# Boost_Stage.net
KiCad netlist of a schematic drawn in Altium Designer
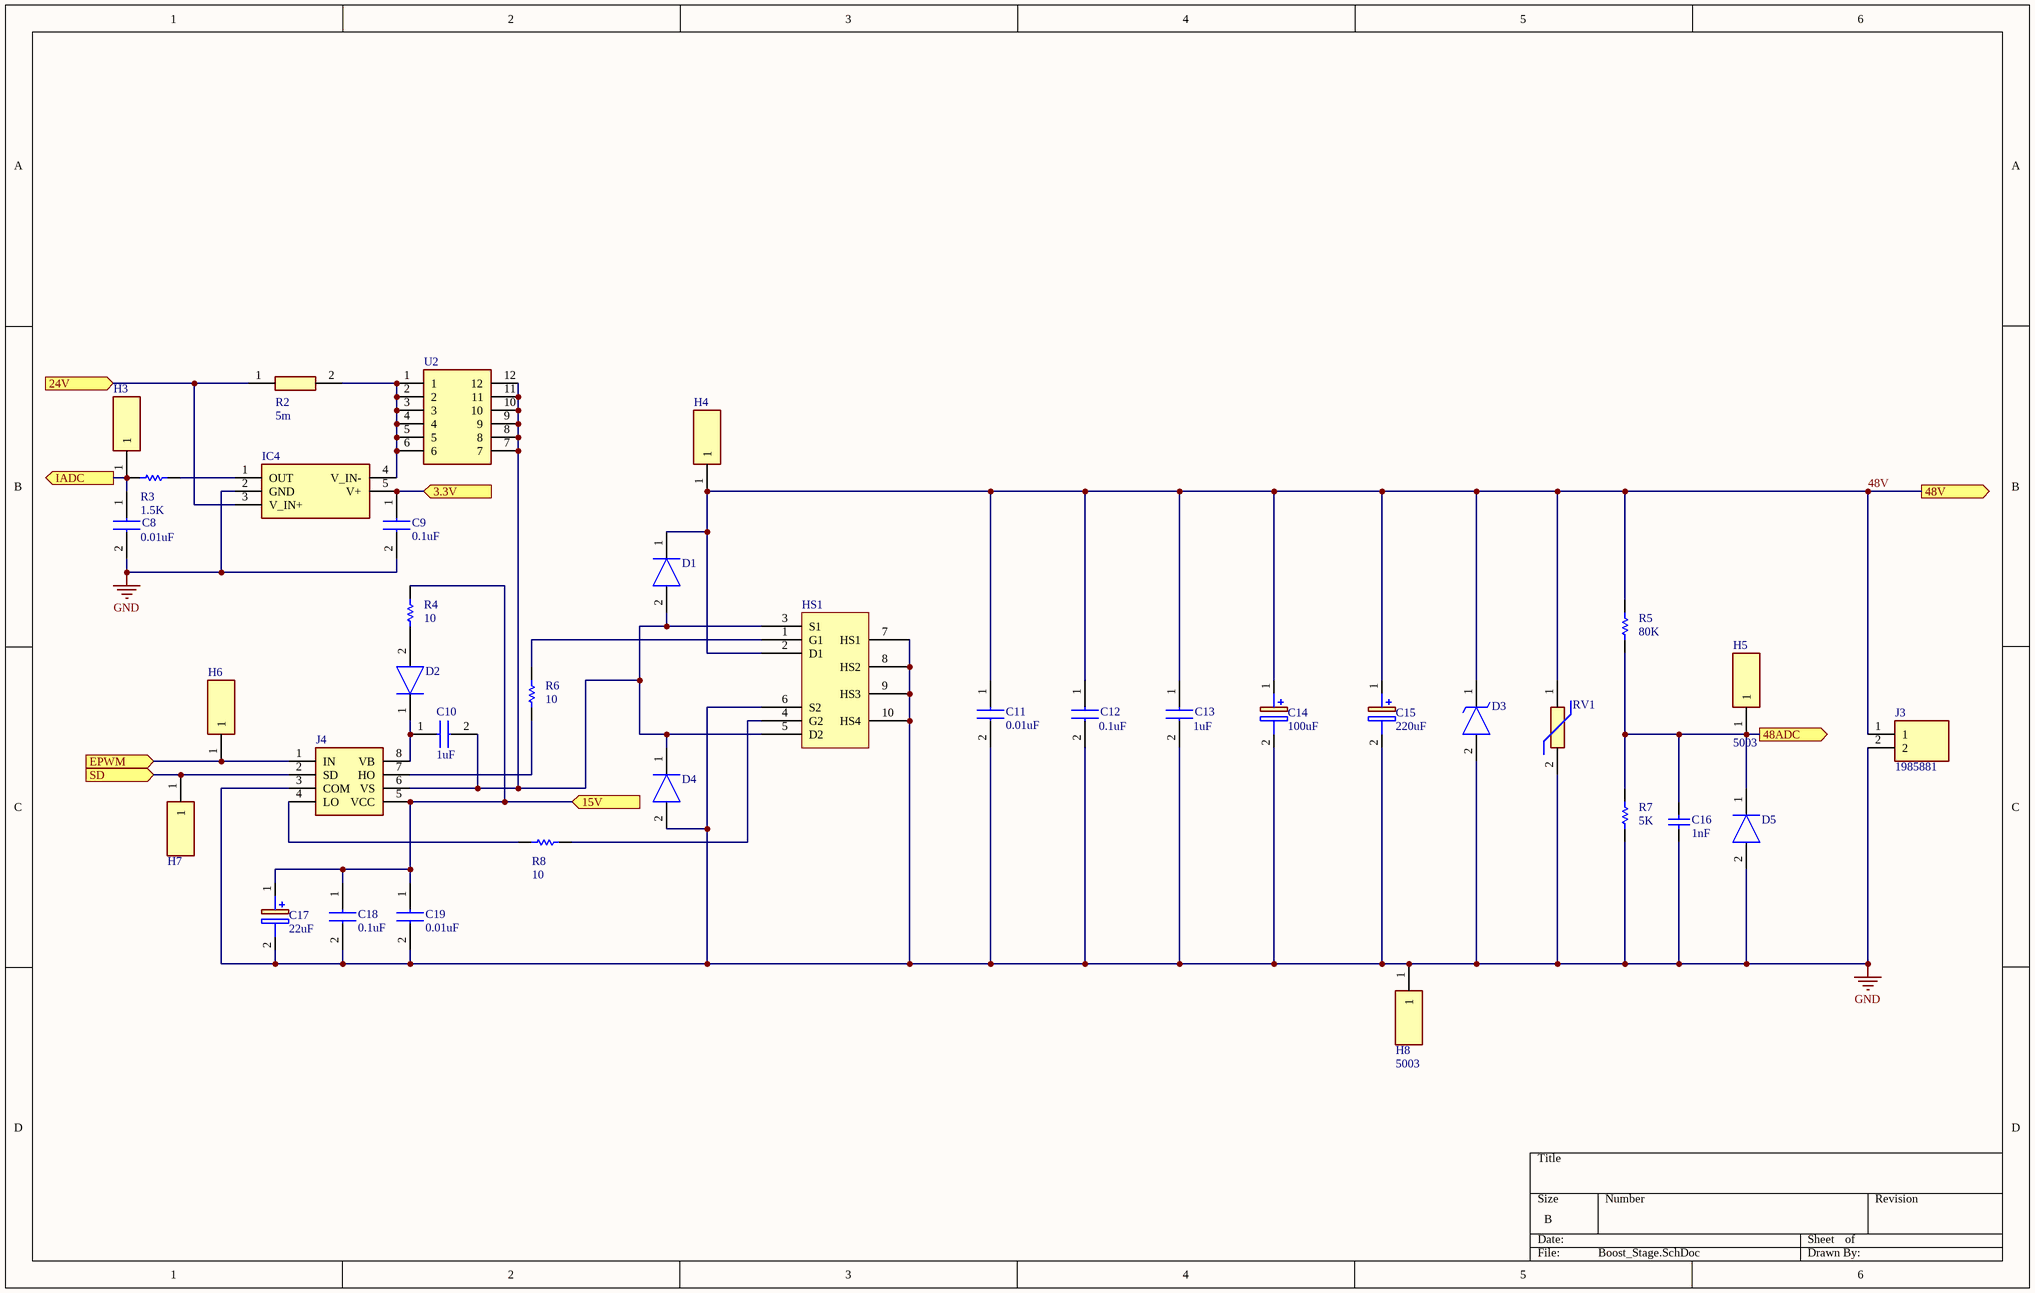
[diagram p0: Boost_Stage.SchDoc]

(export (version "E")
  (design (tool "Eeschema 10.0.6"))
  (components
    (comp (ref "C8")
      (value "0.01uF")
      (footprint "C315C103K5R5TA7990")
      (description "Capacitor 50V")
      (fields (field (name "MANUFACTURER_PART_NUMBER") "C315C103K5R5TA7990"))
      (libsource (lib "ee_453_Schulz") (part "C315C103K5R5TA7990"))
    )
    (comp (ref "C9")
      (value "0.1uF")
      (footprint "K104K10X7RF5UH5")
      (description "Capacitor 50V")
      (fields
        (field (name "MANUFACTURER_PART_NUMBER") "K104K10X7RF5UH5")
        (field (name "MOUSER PART NUMBER") "594-K104K10X7RF5UH5")
      )
      (libsource (lib "ee_453_Schulz") (part "K104K10X7RF5UH5"))
    )
    (comp (ref "C10")
      (value "1uF")
      (footprint "RCE5C1H104J2A2H03B")
      (description "Capacitor")
      (fields
        (field (name "MANUFACTURER_PART_NUMBER") "RDER72A105K2M1H03A")
        (field (name "MOUSER PART NUMBER") "81-RDER72A105K2M1H3A")
      )
      (libsource (lib "ee_453_Schulz") (part "RDER72A105K2M1H03A"))
    )
    (comp (ref "C11")
      (value "0.01uF")
      (footprint "R82(7.2X2.5)")
      (description "Capacitor 100V")
      (fields
        (field (name "MANUFACTURER_PART_NUMBER") "R82EC2100DQ50J")
        (field (name "MOUSER PART NUMBER") "80-R82EC2100DQ50J")
      )
      (libsource (lib "ee_453_Schulz") (part "R82EC2100DQ50J"))
    )
    (comp (ref "C12")
      (value "0.1uF")
      (footprint "ECQE2104JF")
      (description "Capacitor 250V")
      (fields
        (field (name "MANUFACTURER_PART_NUMBER") "ECQ-E2104JF")
        (field (name "MOUSER PART NUMBER") "667-ECQ-E2104JF")
      )
      (libsource (lib "ee_453_Schulz") (part "ECQ-E2104JF"))
    )
    (comp (ref "C13")
      (value "1uF")
      (footprint "ECQE2105KF")
      (description "Capacitor 250V")
      (fields
        (field (name "MANUFACTURER_PART_NUMBER") "ECQ-E2105KF")
        (field (name "MOUSER PART NUMBER") "667-ECQ-E2105KF")
      )
      (libsource (lib "ee_453_Schulz") (part "ECQ-E2105KF"))
    )
    (comp (ref "C14")
      (value "100uF")
      (footprint "CAPPRD500W65D1000H2200")
      (description "Capacitor Polarised 100V")
      (fields
        (field (name "MANUFACTURER_PART_NUMBER") "EEU-FR2A101")
        (field (name "MOUSER PART NUMBER") "667-EEU-FR2A101")
      )
      (libsource (lib "ee_453_Schulz") (part "EEU-FR2A101"))
    )
    (comp (ref "C15")
      (value "220uF")
      (footprint "CAPPRD500W65D1250H2700")
      (description "Capacitor Polarised 100V")
      (fields
        (field (name "MANUFACTURER_PART_NUMBER") "EEU-FS2A221")
        (field (name "MOUSER PART NUMBER") "667-EEU-FS2A221")
      )
      (libsource (lib "ee_453_Schulz") (part "EEU-FS2A221"))
    )
    (comp (ref "C16")
      (value "1nF")
      (footprint "CAPC2013X95X45NL10T25")
      (fields (field (name "PART NUMBER") "GRM2195C2A102JA01D") (field (name "MANUFACTURER") "Murata"))
      (libsource (lib "Altium Content Vault") (part "CAP"))
    )
    (comp (ref "C17")
      (value "22uF")
      (footprint "CAPPRD200W50D550H1250")
      (description "Capacitor Polarised  25V")
      (fields
        (field (name "MANUFACTURER_PART_NUMBER") "UPW1E220MDD")
        (field (name "MOUSER PART NUMBER") "647-UPW1E220MDD")
      )
      (libsource (lib "ee_453_Schulz") (part "UPW1E220MDD"))
    )
    (comp (ref "C18")
      (value "0.1uF")
      (footprint "K104K10X7RF5UH5")
      (description "Capacitor 50V")
      (fields
        (field (name "MANUFACTURER_PART_NUMBER") "K104K10X7RF5UH5")
        (field (name "MOUSER PART NUMBER") "594-K104K10X7RF5UH5")
      )
      (libsource (lib "ee_453_Schulz") (part "K104K10X7RF5UH5"))
    )
    (comp (ref "C19")
      (value "0.01uF")
      (footprint "C315C103K5R5TA7990")
      (description "Capacitor 50V")
      (fields (field (name "MANUFACTURER_PART_NUMBER") "C315C103K5R5TA7990"))
      (libsource (lib "ee_453_Schulz") (part "C315C103K5R5TA7990"))
    )
    (comp (ref "D1")
      (value "S310FA")
      (footprint "SODFL3618X143N")
      (description "Diode")
      (fields (field (name "MOUSER PART NUMBER") "512-S310FA") (field (name "RS PART NUMBER") "1841470"))
      (libsource (lib "ee_453_Schulz") (part "S310FA"))
    )
    (comp (ref "D2")
      (value "1N4003")
      (footprint "DIOAD1413W86L463D238")
      (description "Diode")
      (fields (field (name "MOUSER PART NUMBER") "512-1N4003") (field (name "RS PART NUMBER") "7596674P"))
      (libsource (lib "ee_453_Schulz") (part "1N4003"))
    )
    (comp (ref "D3")
      (value "P6KE91A-E3_54")
      (footprint "DIOAD1910W86L670D310")
      (description "TVS Diode (Uni-directional)")
      (fields (field (name "MANUFACTURER_PART_NUMBER") "P6KE91A-E3/54"))
      (libsource (lib "ee_453_Schulz") (part "P6KE91A-E3_54"))
    )
    (comp (ref "D4")
      (value "S310FA")
      (footprint "SODFL3618X143N")
      (description "Diode")
      (fields (field (name "MOUSER PART NUMBER") "512-S310FA") (field (name "RS PART NUMBER") "1841470"))
      (libsource (lib "ee_453_Schulz") (part "S310FA"))
    )
    (comp (ref "D5")
      (value "BZX584C3V3-G3-08")
      (footprint "SODFL1608X75N")
      (description "Diode")
      (fields (field (name "MOUSER PART NUMBER") "78-BZX584C3V3-G3-08"))
      (libsource (lib "*") (part "BZX584C3V3-G3-08"))
    )
    (comp (ref "H3")
      (value "5003")
      (footprint "5003")
      (description "Hardware")
      (fields (field (name "MOUSER PART NUMBER") "534-5003"))
      (libsource (lib "ee_453_Schulz") (part "5003"))
    )
    (comp (ref "H4")
      (value "5003")
      (footprint "5003")
      (description "Hardware")
      (fields (field (name "MOUSER PART NUMBER") "534-5003"))
      (libsource (lib "ee_453_Schulz") (part "5003"))
    )
    (comp (ref "H5")
      (value "5003")
      (footprint "5003")
      (description "Hardware")
      (fields (field (name "MOUSER PART NUMBER") "534-5003"))
      (libsource (lib "ee_453_Schulz") (part "5003"))
    )
    (comp (ref "H6")
      (value "5003")
      (footprint "5003")
      (description "Hardware")
      (fields (field (name "MOUSER PART NUMBER") "534-5003"))
      (libsource (lib "ee_453_Schulz") (part "5003"))
    )
    (comp (ref "H7")
      (value "5003")
      (footprint "5003")
      (description "Hardware")
      (fields (field (name "MOUSER PART NUMBER") "534-5003"))
      (libsource (lib "") (part "5003_1"))
    )
    (comp (ref "H8")
      (value "5003")
      (footprint "5003")
      (description "Hardware")
      (fields (field (name "MOUSER PART NUMBER") "534-5003"))
      (libsource (lib "") (part "5003_1"))
    )
    (comp (ref "HS1")
      (value "Dual Heatsink")
      (footprint "MOSFETsHeatsink")
      (description "Heat Sink TO-220, TO-247 (Dual) Aluminum 4.0W @ 40°C Board Level, Vertical")
      (libsource (lib "ee_453_Schulz") (part "WV-DT2-101E_1"))
    )
    (comp (ref "IC4")
      (value "INA194AIDBVR")
      (footprint "SOT95P280X145-5N")
      (description "Integrated Circuit")
      (fields (field (name "MOUSER PART NUMBER") "595-INA194AIDBVR"))
      (libsource (lib "ee_453_Schulz") (part "INA194AIDBVR"))
    )
    (comp (ref "J3")
      (value "1985881")
      (footprint "SHDR2W110P0X500_1X2_1000X985X1390P")
      (description "Connector")
      (fields (field (name "MOUSER PART NUMBER") "651-1985881") (field (name "RS PART NUMBER") "4670338"))
      (libsource (lib "ee_453_Schulz") (part "1985881"))
    )
    (comp (ref "J4")
      (value "DILB8P-223TLF")
      (footprint "DIPS762W60P254L1016H525Q8N")
      (description "Connector")
      (fields (field (name "MOUSER2 PART NUMBER") "649-DILB8P223TLF"))
      (libsource (lib "ee_453_Schulz") (part "DILB8P-223TLF"))
    )
    (comp (ref "R2")
      (value "5m")
      (footprint "CRE2512FZR005E3")
      (description "5mOhm Sensing Resistor CRE2512-FZ-R005E-3")
      (fields
        (field (name "MANUFACTURER_PART_NUMBER") "CRE2512-FZ-R005E-3")
        (field (name "MOUSER PART NUMBER") "652-CRE2512FZR005E-3")
      )
      (libsource (lib "ee_453_Schulz") (part "CRE2512-FZ-R005E-3"))
    )
    (comp (ref "R3")
      (value "1.5K")
      (footprint "AXIAL-0.3")
      (description "Resistor")
      (fields (field (name "Comment") "Res1") (field (name "PUBLISHER") "Altium Limited"))
      (libsource (lib "Miscellaneous Devices") (part "Res1"))
    )
    (comp (ref "R4")
      (value "10")
      (footprint "AXIAL-0.3")
      (description "Resistor")
      (fields (field (name "Comment") "Res1") (field (name "PUBLISHER") "Altium Limited"))
      (libsource (lib "Miscellaneous Devices") (part "Res1"))
    )
    (comp (ref "R5")
      (value "80K")
      (footprint "AXIAL-0.3")
      (description "Resistor")
      (fields (field (name "Comment") "Res1") (field (name "PUBLISHER") "Altium Limited"))
      (libsource (lib "Miscellaneous Devices") (part "Res1"))
    )
    (comp (ref "R6")
      (value "10")
      (footprint "AXIAL-0.3")
      (description "Resistor")
      (fields (field (name "Comment") "Res1") (field (name "PUBLISHER") "Altium Limited"))
      (libsource (lib "Miscellaneous Devices") (part "Res1"))
    )
    (comp (ref "R7")
      (value "5K")
      (footprint "AXIAL-0.3")
      (description "Resistor")
      (fields (field (name "Comment") "Res1") (field (name "PUBLISHER") "Altium Limited"))
      (libsource (lib "Miscellaneous Devices") (part "Res1"))
    )
    (comp (ref "R8")
      (value "10")
      (footprint "AXIAL-0.3")
      (description "Resistor")
      (fields (field (name "Comment") "Res1") (field (name "PUBLISHER") "Altium Limited"))
      (libsource (lib "Miscellaneous Devices") (part "Res1"))
    )
    (comp (ref "RV1")
      (value "V68ZS10P")
      (footprint "V68ZS10P")
      (description "Varistor")
      (libsource (lib "ee_453_Schulz") (part "V68ZS10P"))
    )
    (comp (ref "U2")
      (value "B65878E1012D001")
      (footprint "B65878E1012D001")
      (description "Undefined or Miscellaneous")
      (fields
        (field (name "MOUSER PART NUMBER") "871-B65878E1012D001")
        (field (name "RS PART NUMBER") "1253423")
      )
      (libsource (lib "ee_453_Schulz") (part "B65878E1012D001"))
    )
  )
  (nets
    (net (code "1") (name "/3.3V") (class "Default")
      (node (ref "C9") (pin "1") (pinfunction "1_1") (pintype "passive"))
      (node (ref "IC4") (pin "5") (pinfunction "V+_5") (pintype "passive"))
    )
    (net (code "2") (name "/15V") (class "Default")
      (node (ref "C17") (pin "1") (pinfunction "+_1") (pintype "passive"))
      (node (ref "C18") (pin "1") (pinfunction "1_1") (pintype "passive"))
      (node (ref "C19") (pin "1") (pinfunction "1_1") (pintype "passive"))
      (node (ref "J4") (pin "5") (pinfunction "VCC_5") (pintype "passive"))
      (node (ref "R4") (pin "2") (pinfunction "2_2") (pintype "passive"))
    )
    (net (code "3") (name "/24V") (class "Default")
      (node (ref "IC4") (pin "3") (pinfunction "V_IN+_3") (pintype "passive"))
      (node (ref "R2") (pin "1") (pinfunction "1_1") (pintype "passive"))
    )
    (net (code "4") (name "/48ADC") (class "Default")
      (node (ref "C16") (pin "2") (pinfunction "2_2") (pintype "passive"))
      (node (ref "D5") (pin "1") (pinfunction "K_1") (pintype "passive"))
      (node (ref "H5") (pin "1") (pinfunction "1_1") (pintype "passive"))
      (node (ref "R5") (pin "1") (pinfunction "1_1") (pintype "passive"))
      (node (ref "R7") (pin "2") (pinfunction "2_2") (pintype "passive"))
    )
    (net (code "5") (name "/48V") (class "Default")
      (node (ref "C11") (pin "1") (pinfunction "1_1") (pintype "passive"))
      (node (ref "C12") (pin "1") (pinfunction "1_1") (pintype "passive"))
      (node (ref "C13") (pin "1") (pinfunction "1_1") (pintype "passive"))
      (node (ref "C14") (pin "1") (pinfunction "+_1") (pintype "passive"))
      (node (ref "C15") (pin "1") (pinfunction "+_1") (pintype "passive"))
      (node (ref "D1") (pin "1") (pinfunction "K_1") (pintype "passive"))
      (node (ref "D3") (pin "1") (pinfunction "K_1") (pintype "passive"))
      (node (ref "H4") (pin "1") (pinfunction "1_1") (pintype "passive"))
      (node (ref "HS1") (pin "2") (pinfunction "D1_2") (pintype "passive"))
      (node (ref "J3") (pin "1") (pinfunction "1_1") (pintype "passive"))
      (node (ref "R5") (pin "2") (pinfunction "2_2") (pintype "passive"))
      (node (ref "RV1") (pin "1") (pinfunction "1_1") (pintype "passive"))
    )
    (net (code "6") (name "/EPWM") (class "Default")
      (node (ref "H6") (pin "1") (pinfunction "1_1") (pintype "passive"))
      (node (ref "J4") (pin "1") (pinfunction "IN_1") (pintype "passive"))
    )
    (net (code "7") (name "/IADC") (class "Default")
      (node (ref "C8") (pin "1") (pinfunction "1_1") (pintype "passive"))
      (node (ref "H3") (pin "1") (pinfunction "1_1") (pintype "passive"))
      (node (ref "R3") (pin "2") (pinfunction "2_2") (pintype "passive"))
    )
    (net (code "8") (name "/SD") (class "Default")
      (node (ref "H7") (pin "1") (pinfunction "1_1") (pintype "passive"))
      (node (ref "J4") (pin "2") (pinfunction "SD_2") (pintype "passive"))
    )
    (net (code "9") (name "GND") (class "Default")
      (node (ref "C11") (pin "2") (pinfunction "2_2") (pintype "passive"))
      (node (ref "C12") (pin "2") (pinfunction "2_2") (pintype "passive"))
      (node (ref "C13") (pin "2") (pinfunction "2_2") (pintype "passive"))
      (node (ref "C14") (pin "2") (pinfunction "-_2") (pintype "passive"))
      (node (ref "C15") (pin "2") (pinfunction "-_2") (pintype "passive"))
      (node (ref "C16") (pin "1") (pinfunction "1_1") (pintype "passive"))
      (node (ref "C17") (pin "2") (pinfunction "-_2") (pintype "passive"))
      (node (ref "C18") (pin "2") (pinfunction "2_2") (pintype "passive"))
      (node (ref "C19") (pin "2") (pinfunction "2_2") (pintype "passive"))
      (node (ref "C8") (pin "2") (pinfunction "2_2") (pintype "passive"))
      (node (ref "C9") (pin "2") (pinfunction "2_2") (pintype "passive"))
      (node (ref "D3") (pin "2") (pinfunction "A_2") (pintype "passive"))
      (node (ref "D4") (pin "2") (pinfunction "A_2") (pintype "passive"))
      (node (ref "D5") (pin "2") (pinfunction "A_2") (pintype "passive"))
      (node (ref "H8") (pin "1") (pinfunction "1_1") (pintype "passive"))
      (node (ref "HS1") (pin "10") (pinfunction "HS4_10") (pintype "passive"))
      (node (ref "HS1") (pin "6") (pinfunction "S2_6") (pintype "passive"))
      (node (ref "HS1") (pin "7") (pinfunction "HS1_7") (pintype "passive"))
      (node (ref "HS1") (pin "8") (pinfunction "HS2_8") (pintype "passive"))
      (node (ref "HS1") (pin "9") (pinfunction "HS3_9") (pintype "passive"))
      (node (ref "IC4") (pin "2") (pinfunction "GND_2") (pintype "passive"))
      (node (ref "J3") (pin "2") (pinfunction "2_2") (pintype "passive"))
      (node (ref "J4") (pin "3") (pinfunction "COM_3") (pintype "passive"))
      (node (ref "R7") (pin "1") (pinfunction "1_1") (pintype "passive"))
      (node (ref "RV1") (pin "2") (pinfunction "2_2") (pintype "passive"))
    )
    (net (code "10") (name "Net-(D1-A)") (class "Default")
      (node (ref "C10") (pin "2") (pinfunction "2_2") (pintype "passive"))
      (node (ref "D1") (pin "2") (pinfunction "A_2") (pintype "passive"))
      (node (ref "D4") (pin "1") (pinfunction "K_1") (pintype "passive"))
      (node (ref "HS1") (pin "3") (pinfunction "S1_3") (pintype "passive"))
      (node (ref "HS1") (pin "5") (pinfunction "D2_5") (pintype "passive"))
      (node (ref "J4") (pin "6") (pinfunction "VS_6") (pintype "passive"))
      (node (ref "U2") (pin "10") (pinfunction "10_10") (pintype "passive"))
      (node (ref "U2") (pin "11") (pinfunction "11_11") (pintype "passive"))
      (node (ref "U2") (pin "12") (pinfunction "12_12") (pintype "passive"))
      (node (ref "U2") (pin "7") (pinfunction "7_7") (pintype "passive"))
      (node (ref "U2") (pin "8") (pinfunction "8_8") (pintype "passive"))
      (node (ref "U2") (pin "9") (pinfunction "9_9") (pintype "passive"))
    )
    (net (code "11") (name "Net-(D2-A)") (class "Default")
      (node (ref "D2") (pin "2") (pinfunction "A_2") (pintype "passive"))
      (node (ref "R4") (pin "1") (pinfunction "1_1") (pintype "passive"))
    )
    (net (code "12") (name "Net-(D2-K)") (class "Default")
      (node (ref "C10") (pin "1") (pinfunction "1_1") (pintype "passive"))
      (node (ref "D2") (pin "1") (pinfunction "K_1") (pintype "passive"))
      (node (ref "J4") (pin "8") (pinfunction "VB_8") (pintype "passive"))
    )
    (net (code "13") (name "Net-(HS1-G1)") (class "Default")
      (node (ref "HS1") (pin "1") (pinfunction "G1_1") (pintype "passive"))
      (node (ref "R6") (pin "2") (pinfunction "2_2") (pintype "passive"))
    )
    (net (code "14") (name "Net-(HS1-G2)") (class "Default")
      (node (ref "HS1") (pin "4") (pinfunction "G2_4") (pintype "passive"))
      (node (ref "R8") (pin "1") (pinfunction "1_1") (pintype "passive"))
    )
    (net (code "15") (name "Net-(IC4-OUT)") (class "Default")
      (node (ref "IC4") (pin "1") (pinfunction "OUT_1") (pintype "passive"))
      (node (ref "R3") (pin "1") (pinfunction "1_1") (pintype "passive"))
    )
    (net (code "16") (name "Net-(IC4-V_IN-)") (class "Default")
      (node (ref "IC4") (pin "4") (pinfunction "V_IN-_4") (pintype "passive"))
      (node (ref "R2") (pin "2") (pinfunction "2_2") (pintype "passive"))
      (node (ref "U2") (pin "1") (pinfunction "1_1") (pintype "passive"))
      (node (ref "U2") (pin "2") (pinfunction "2_2") (pintype "passive"))
      (node (ref "U2") (pin "3") (pinfunction "3_3") (pintype "passive"))
      (node (ref "U2") (pin "4") (pinfunction "4_4") (pintype "passive"))
      (node (ref "U2") (pin "5") (pinfunction "5_5") (pintype "passive"))
      (node (ref "U2") (pin "6") (pinfunction "6_6") (pintype "passive"))
    )
    (net (code "17") (name "Net-(J4-HO)") (class "Default")
      (node (ref "J4") (pin "7") (pinfunction "HO_7") (pintype "passive"))
      (node (ref "R6") (pin "1") (pinfunction "1_1") (pintype "passive"))
    )
    (net (code "18") (name "Net-(J4-LO)") (class "Default")
      (node (ref "J4") (pin "4") (pinfunction "LO_4") (pintype "passive"))
      (node (ref "R8") (pin "2") (pinfunction "2_2") (pintype "passive"))
    )
  )
)
